# ESIMA_NFC-Verbindungsleitung.net
KiCad netlist of a schematic drawn in Altium Designer
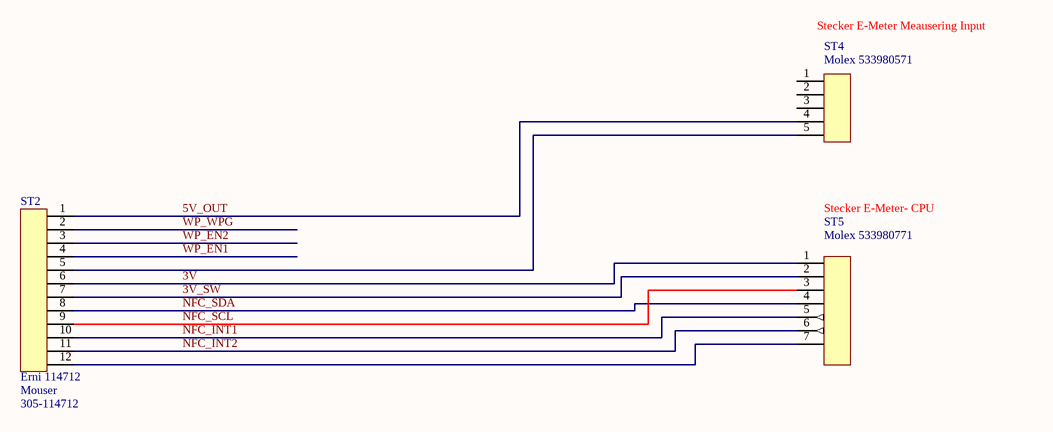
[diagram p0: ESIMA NFC-Verbindungsleitung.SchDoc]

(export (version "E")
  (design (tool "Eeschema 10.0.6"))
  (components
    (comp (ref "ST2")
      (value "Erni 114712")
      (footprint "Erni 114712")
      (description "Erni MicroStac 12pol, 0.8mm Raster")
      (fields (field (name "SUPPLIER 1") "Mouser") (field (name "SUPPLIER PART NUMBER 1") "305-114712"))
      (libsource (lib "JM_Elektromechanik") (part "Erni 114712"))
    )
    (comp (ref "ST4")
      (value "Molex 533980571")
      (footprint "Molex 533980571")
      (description "MOLEX - 53398-0571 - STIFTLEISTE, SMT, 1.25MM, 5POL")
      (libsource (lib "JM_Elektromechanik") (part "Molex 533980571"))
    )
    (comp (ref "ST5")
      (value "Molex 533980771")
      (footprint "Molex 533980771")
      (description "Molex Pico 7Pol Blade SMD gerade 533980771")
      (libsource (lib "JM_Elektromechanik") (part "Molex 533980771"))
    )
  )
  (nets
    (net (code "1") (name "/3V") (class "Default")
      (node (ref "ST2") (pin "6") (pinfunction "6_6") (pintype "passive"))
      (node (ref "ST5") (pin "1") (pinfunction "1_1") (pintype "passive"))
    )
    (net (code "2") (name "/3V_SW") (class "Default")
      (node (ref "ST2") (pin "7") (pinfunction "7_7") (pintype "passive"))
      (node (ref "ST5") (pin "2") (pinfunction "2_2") (pintype "passive"))
    )
    (net (code "3") (name "/5V_OUT") (class "Default")
      (node (ref "ST2") (pin "1") (pinfunction "1_1") (pintype "passive"))
      (node (ref "ST4") (pin "4") (pinfunction "4_4") (pintype "passive"))
    )
    (net (code "4") (name "/NFC_INT1") (class "Default")
      (node (ref "ST2") (pin "10") (pinfunction "10_10") (pintype "passive"))
      (node (ref "ST5") (pin "5") (pinfunction "5_5") (pintype "output"))
    )
    (net (code "5") (name "/NFC_INT2") (class "Default")
      (node (ref "ST2") (pin "11") (pinfunction "11_11") (pintype "passive"))
      (node (ref "ST5") (pin "6") (pinfunction "6_6") (pintype "output"))
    )
    (net (code "6") (name "/NFC_SCL") (class "Default")
      (node (ref "ST2") (pin "9") (pinfunction "9_9") (pintype "passive"))
      (node (ref "ST5") (pin "3") (pinfunction "3_3") (pintype "passive"))
    )
    (net (code "7") (name "/NFC_SDA") (class "Default")
      (node (ref "ST2") (pin "8") (pinfunction "8_8") (pintype "passive"))
      (node (ref "ST5") (pin "4") (pinfunction "4_4") (pintype "passive"))
    )
    (net (code "8") (name "/WP_EN1") (class "Default")
      (node (ref "ST2") (pin "4") (pinfunction "4_4") (pintype "passive"))
    )
    (net (code "9") (name "/WP_EN2") (class "Default")
      (node (ref "ST2") (pin "3") (pinfunction "3_3") (pintype "passive"))
    )
    (net (code "10") (name "/WP_~{WPG}") (class "Default")
      (node (ref "ST2") (pin "2") (pinfunction "2_2") (pintype "passive"))
    )
    (net (code "11") (name "Net-(ST2-Pad5)") (class "Default")
      (node (ref "ST2") (pin "5") (pinfunction "5_5") (pintype "passive"))
      (node (ref "ST4") (pin "5") (pinfunction "5_5") (pintype "passive"))
    )
    (net (code "12") (name "Net-(ST2-Pad12)") (class "Default")
      (node (ref "ST2") (pin "12") (pinfunction "12_12") (pintype "passive"))
      (node (ref "ST5") (pin "7") (pinfunction "7_7") (pintype "passive"))
    )
    (net (code "13") (name "unconnected-(ST2-Pad13)") (class "Default")
      (node (ref "ST2") (pin "13") (pinfunction "13_13") (pintype "passive"))
    )
    (net (code "14") (name "unconnected-(ST2-Pad14)") (class "Default")
      (node (ref "ST2") (pin "14") (pinfunction "14_14") (pintype "passive"))
    )
    (net (code "15") (name "unconnected-(ST4-Pad1)") (class "Default")
      (node (ref "ST4") (pin "1") (pinfunction "1_1") (pintype "passive"))
    )
    (net (code "16") (name "unconnected-(ST4-Pad2)") (class "Default")
      (node (ref "ST4") (pin "2") (pinfunction "2_2") (pintype "passive"))
    )
    (net (code "17") (name "unconnected-(ST4-Pad3)") (class "Default")
      (node (ref "ST4") (pin "3") (pinfunction "3_3") (pintype "passive"))
    )
    (net (code "18") (name "unconnected-(ST4-Pad6)") (class "Default")
      (node (ref "ST4") (pin "6") (pinfunction "6_6") (pintype "passive"))
    )
    (net (code "19") (name "unconnected-(ST4-Pad7)") (class "Default")
      (node (ref "ST4") (pin "7") (pinfunction "7_7") (pintype "passive"))
    )
    (net (code "20") (name "unconnected-(ST5-Pad8)") (class "Default")
      (node (ref "ST5") (pin "8") (pinfunction "8_8") (pintype "passive"))
    )
    (net (code "21") (name "unconnected-(ST5-Pad9)") (class "Default")
      (node (ref "ST5") (pin "9") (pinfunction "9_9") (pintype "passive"))
    )
  )
)
